# hotswap.net
KiCad netlist of a schematic drawn in EAGLE
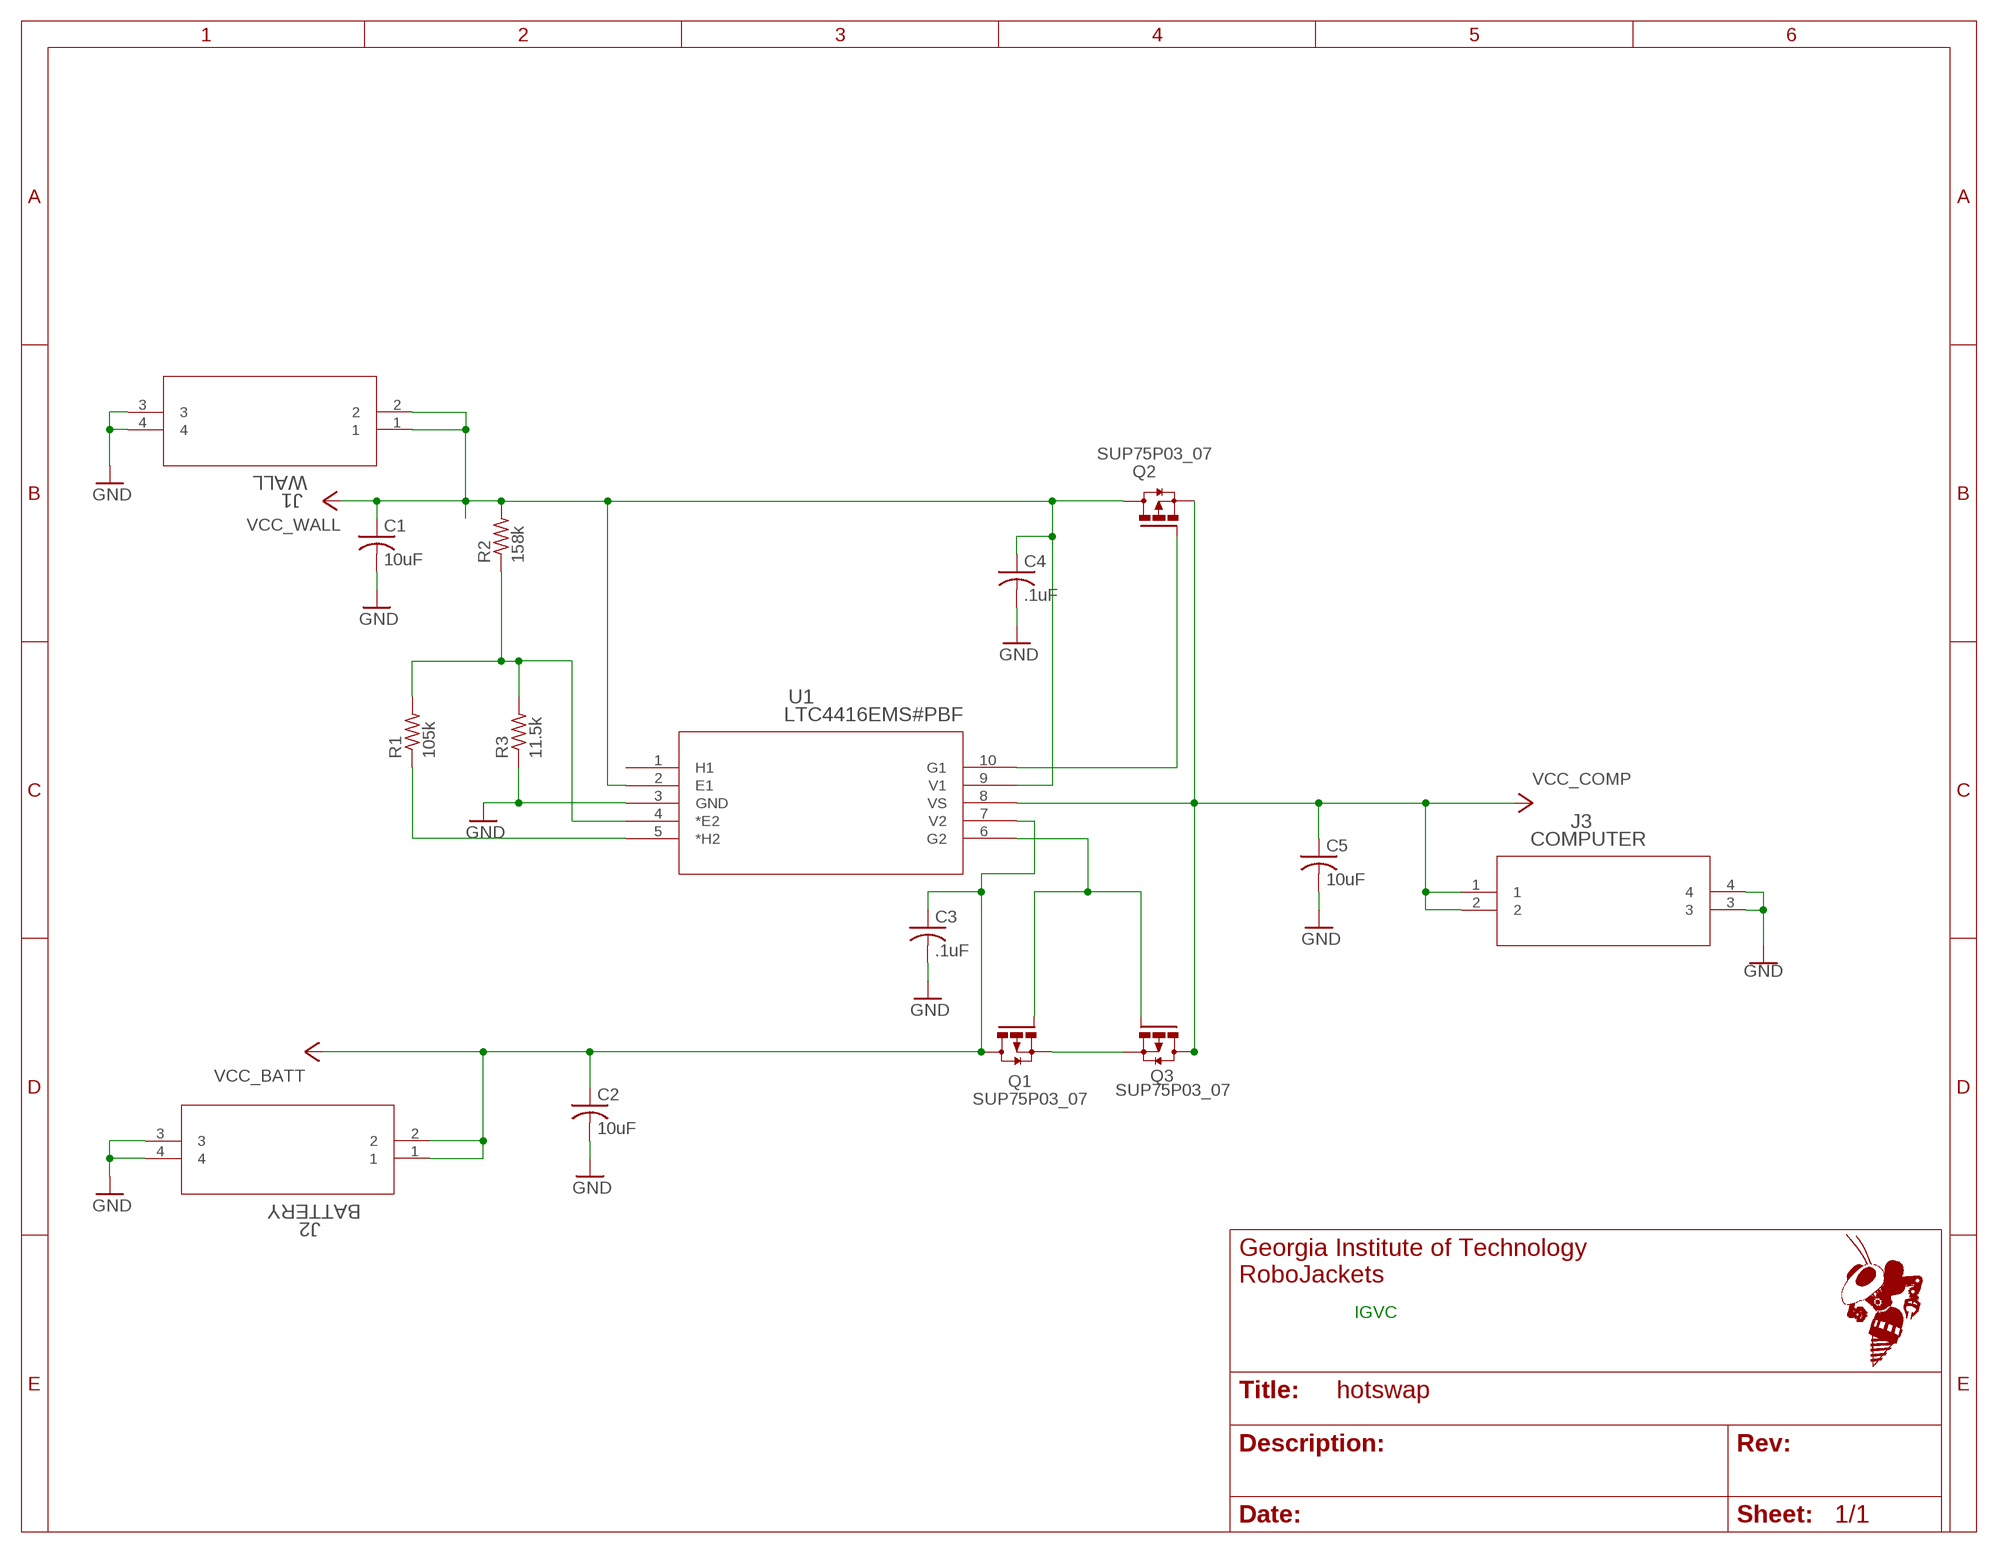
[diagram p0: schematic, sheet 1]

(export (version "E")
  (design (tool "Eeschema 10.0.6"))
  (components
    (comp (ref "C1")
      (value "10uF")
      (footprint "eagle-import:C1210")
      (libsource (lib "eagle-import") (part "C-USC1210"))
    )
    (comp (ref "C2")
      (value "10uF")
      (footprint "eagle-import:C1210")
      (libsource (lib "eagle-import") (part "C-USC1210"))
    )
    (comp (ref "C3")
      (value ".1uF")
      (footprint "eagle-import:C0805")
      (libsource (lib "eagle-import") (part "C-USC0805"))
    )
    (comp (ref "C4")
      (value ".1uF")
      (footprint "eagle-import:C0805")
      (libsource (lib "eagle-import") (part "C-USC0805"))
    )
    (comp (ref "C5")
      (value "10uF")
      (footprint "eagle-import:C1210")
      (libsource (lib "eagle-import") (part "C-USC1210"))
    )
    (comp (ref "J1")
      (value "WALL")
      (footprint "eagle-import:641737-1")
      (fields (field (name "MANUFACTURER_PART_NUMBER") "6417371"))
      (libsource (lib "eagle-import") (part "641737-1"))
    )
    (comp (ref "J2")
      (value "BATTERY")
      (footprint "eagle-import:641737-1")
      (fields (field (name "MANUFACTURER_PART_NUMBER") "6417371"))
      (libsource (lib "eagle-import") (part "641737-1"))
    )
    (comp (ref "J3")
      (value "COMPUTER")
      (footprint "eagle-import:641737-1")
      (fields (field (name "MANUFACTURER_PART_NUMBER") "6417371"))
      (libsource (lib "eagle-import") (part "641737-1"))
    )
    (comp (ref "Q1")
      (value "SUP75P03_07")
      (footprint "eagle-import:DPACK_2")
      (libsource (lib "eagle-import") (part "SUP75P03_07"))
    )
    (comp (ref "Q2")
      (value "SUP75P03_07")
      (footprint "eagle-import:DPACK_2")
      (libsource (lib "eagle-import") (part "SUP75P03_07"))
    )
    (comp (ref "Q3")
      (value "SUP75P03_07")
      (footprint "eagle-import:DPACK_2")
      (libsource (lib "eagle-import") (part "SUP75P03_07"))
    )
    (comp (ref "R1")
      (value "105k")
      (footprint "eagle-import:R0603")
      (libsource (lib "eagle-import") (part "R-US_R0603"))
    )
    (comp (ref "R2")
      (value "158k")
      (footprint "eagle-import:R0603")
      (libsource (lib "eagle-import") (part "R-US_R0603"))
    )
    (comp (ref "R3")
      (value "11.5k")
      (footprint "eagle-import:R0603")
      (libsource (lib "eagle-import") (part "R-US_R0603"))
    )
    (comp (ref "U1")
      (value "LTC4416EMS#PBF")
      (footprint "eagle-import:MSOP-10_MS")
      (fields
        (field (name "DIGI-KEY_PART_NUMBER") "LTC4416EMS#PBF-ND")
        (field (name "MF") "Linear Technology")
      )
      (libsource (lib "eagle-import") (part "LTC4416EMS#PBF"))
    )
  )
  (nets
    (net (code "1") (name "GND") (class "Default")
      (node (ref "C1") (pin "2") (pinfunction "2_2") (pintype "passive"))
      (node (ref "C2") (pin "2") (pinfunction "2_2") (pintype "passive"))
      (node (ref "C3") (pin "2") (pinfunction "2_2") (pintype "passive"))
      (node (ref "C4") (pin "2") (pinfunction "2_2") (pintype "passive"))
      (node (ref "C5") (pin "2") (pinfunction "2_2") (pintype "passive"))
      (node (ref "J1") (pin "3") (pinfunction "3_3") (pintype "passive"))
      (node (ref "J1") (pin "4") (pinfunction "4_4") (pintype "passive"))
      (node (ref "J2") (pin "3") (pinfunction "3_3") (pintype "passive"))
      (node (ref "J2") (pin "4") (pinfunction "4_4") (pintype "passive"))
      (node (ref "J3") (pin "3") (pinfunction "3_3") (pintype "passive"))
      (node (ref "J3") (pin "4") (pinfunction "4_4") (pintype "passive"))
      (node (ref "R3") (pin "1") (pinfunction "1_1") (pintype "passive"))
      (node (ref "U1") (pin "3") (pinfunction "GND_3") (pintype "power_in"))
    )
    (net (code "2") (name "Net-(Q1-PadS)") (class "Default")
      (node (ref "Q1") (pin "S") (pinfunction "S_S") (pintype "passive"))
      (node (ref "Q3") (pin "S") (pinfunction "S_S") (pintype "passive"))
    )
    (net (code "3") (name "Net-(U1-*E2)") (class "Default")
      (node (ref "R1") (pin "2") (pinfunction "2_2") (pintype "passive"))
      (node (ref "R2") (pin "1") (pinfunction "1_1") (pintype "passive"))
      (node (ref "R3") (pin "2") (pinfunction "2_2") (pintype "passive"))
      (node (ref "U1") (pin "4") (pinfunction "*E2_4") (pintype "input"))
    )
    (net (code "4") (name "Net-(U1-*H2)") (class "Default")
      (node (ref "R1") (pin "1") (pinfunction "1_1") (pintype "passive"))
      (node (ref "U1") (pin "5") (pinfunction "*H2_5") (pintype "input"))
    )
    (net (code "5") (name "Net-(U1-G1)") (class "Default")
      (node (ref "Q2") (pin "G") (pinfunction "G_G") (pintype "passive"))
      (node (ref "U1") (pin "10") (pinfunction "G1_10") (pintype "passive"))
    )
    (net (code "6") (name "Net-(U1-G2)") (class "Default")
      (node (ref "Q1") (pin "G") (pinfunction "G_G") (pintype "passive"))
      (node (ref "Q3") (pin "G") (pinfunction "G_G") (pintype "passive"))
      (node (ref "U1") (pin "6") (pinfunction "G2_6") (pintype "passive"))
    )
    (net (code "7") (name "VCC_BATT") (class "Default")
      (node (ref "C2") (pin "1") (pinfunction "1_1") (pintype "passive"))
      (node (ref "C3") (pin "1") (pinfunction "1_1") (pintype "passive"))
      (node (ref "J2") (pin "1") (pinfunction "1_1") (pintype "passive"))
      (node (ref "J2") (pin "2") (pinfunction "2_2") (pintype "passive"))
      (node (ref "Q1") (pin "D") (pinfunction "D_D") (pintype "passive"))
      (node (ref "U1") (pin "7") (pinfunction "V2_7") (pintype "input"))
    )
    (net (code "8") (name "VCC_COMP") (class "Default")
      (node (ref "C5") (pin "1") (pinfunction "1_1") (pintype "passive"))
      (node (ref "J3") (pin "1") (pinfunction "1_1") (pintype "passive"))
      (node (ref "J3") (pin "2") (pinfunction "2_2") (pintype "passive"))
      (node (ref "Q2") (pin "S") (pinfunction "S_S") (pintype "passive"))
      (node (ref "Q3") (pin "D") (pinfunction "D_D") (pintype "passive"))
      (node (ref "U1") (pin "8") (pinfunction "VS_8") (pintype "input"))
    )
    (net (code "9") (name "VCC_WALL") (class "Default")
      (node (ref "C1") (pin "1") (pinfunction "1_1") (pintype "passive"))
      (node (ref "C4") (pin "1") (pinfunction "1_1") (pintype "passive"))
      (node (ref "J1") (pin "1") (pinfunction "1_1") (pintype "passive"))
      (node (ref "J1") (pin "2") (pinfunction "2_2") (pintype "passive"))
      (node (ref "Q2") (pin "D") (pinfunction "D_D") (pintype "passive"))
      (node (ref "R2") (pin "2") (pinfunction "2_2") (pintype "passive"))
      (node (ref "U1") (pin "2") (pinfunction "E1_2") (pintype "input"))
      (node (ref "U1") (pin "9") (pinfunction "V1_9") (pintype "input"))
    )
    (net (code "10") (name "unconnected-(U1-H1-Pad1)") (class "Default")
      (node (ref "U1") (pin "1") (pinfunction "H1_1") (pintype "output"))
    )
  )
)
